# Sheet1.net
KiCad netlist of a schematic drawn in Altium Designer
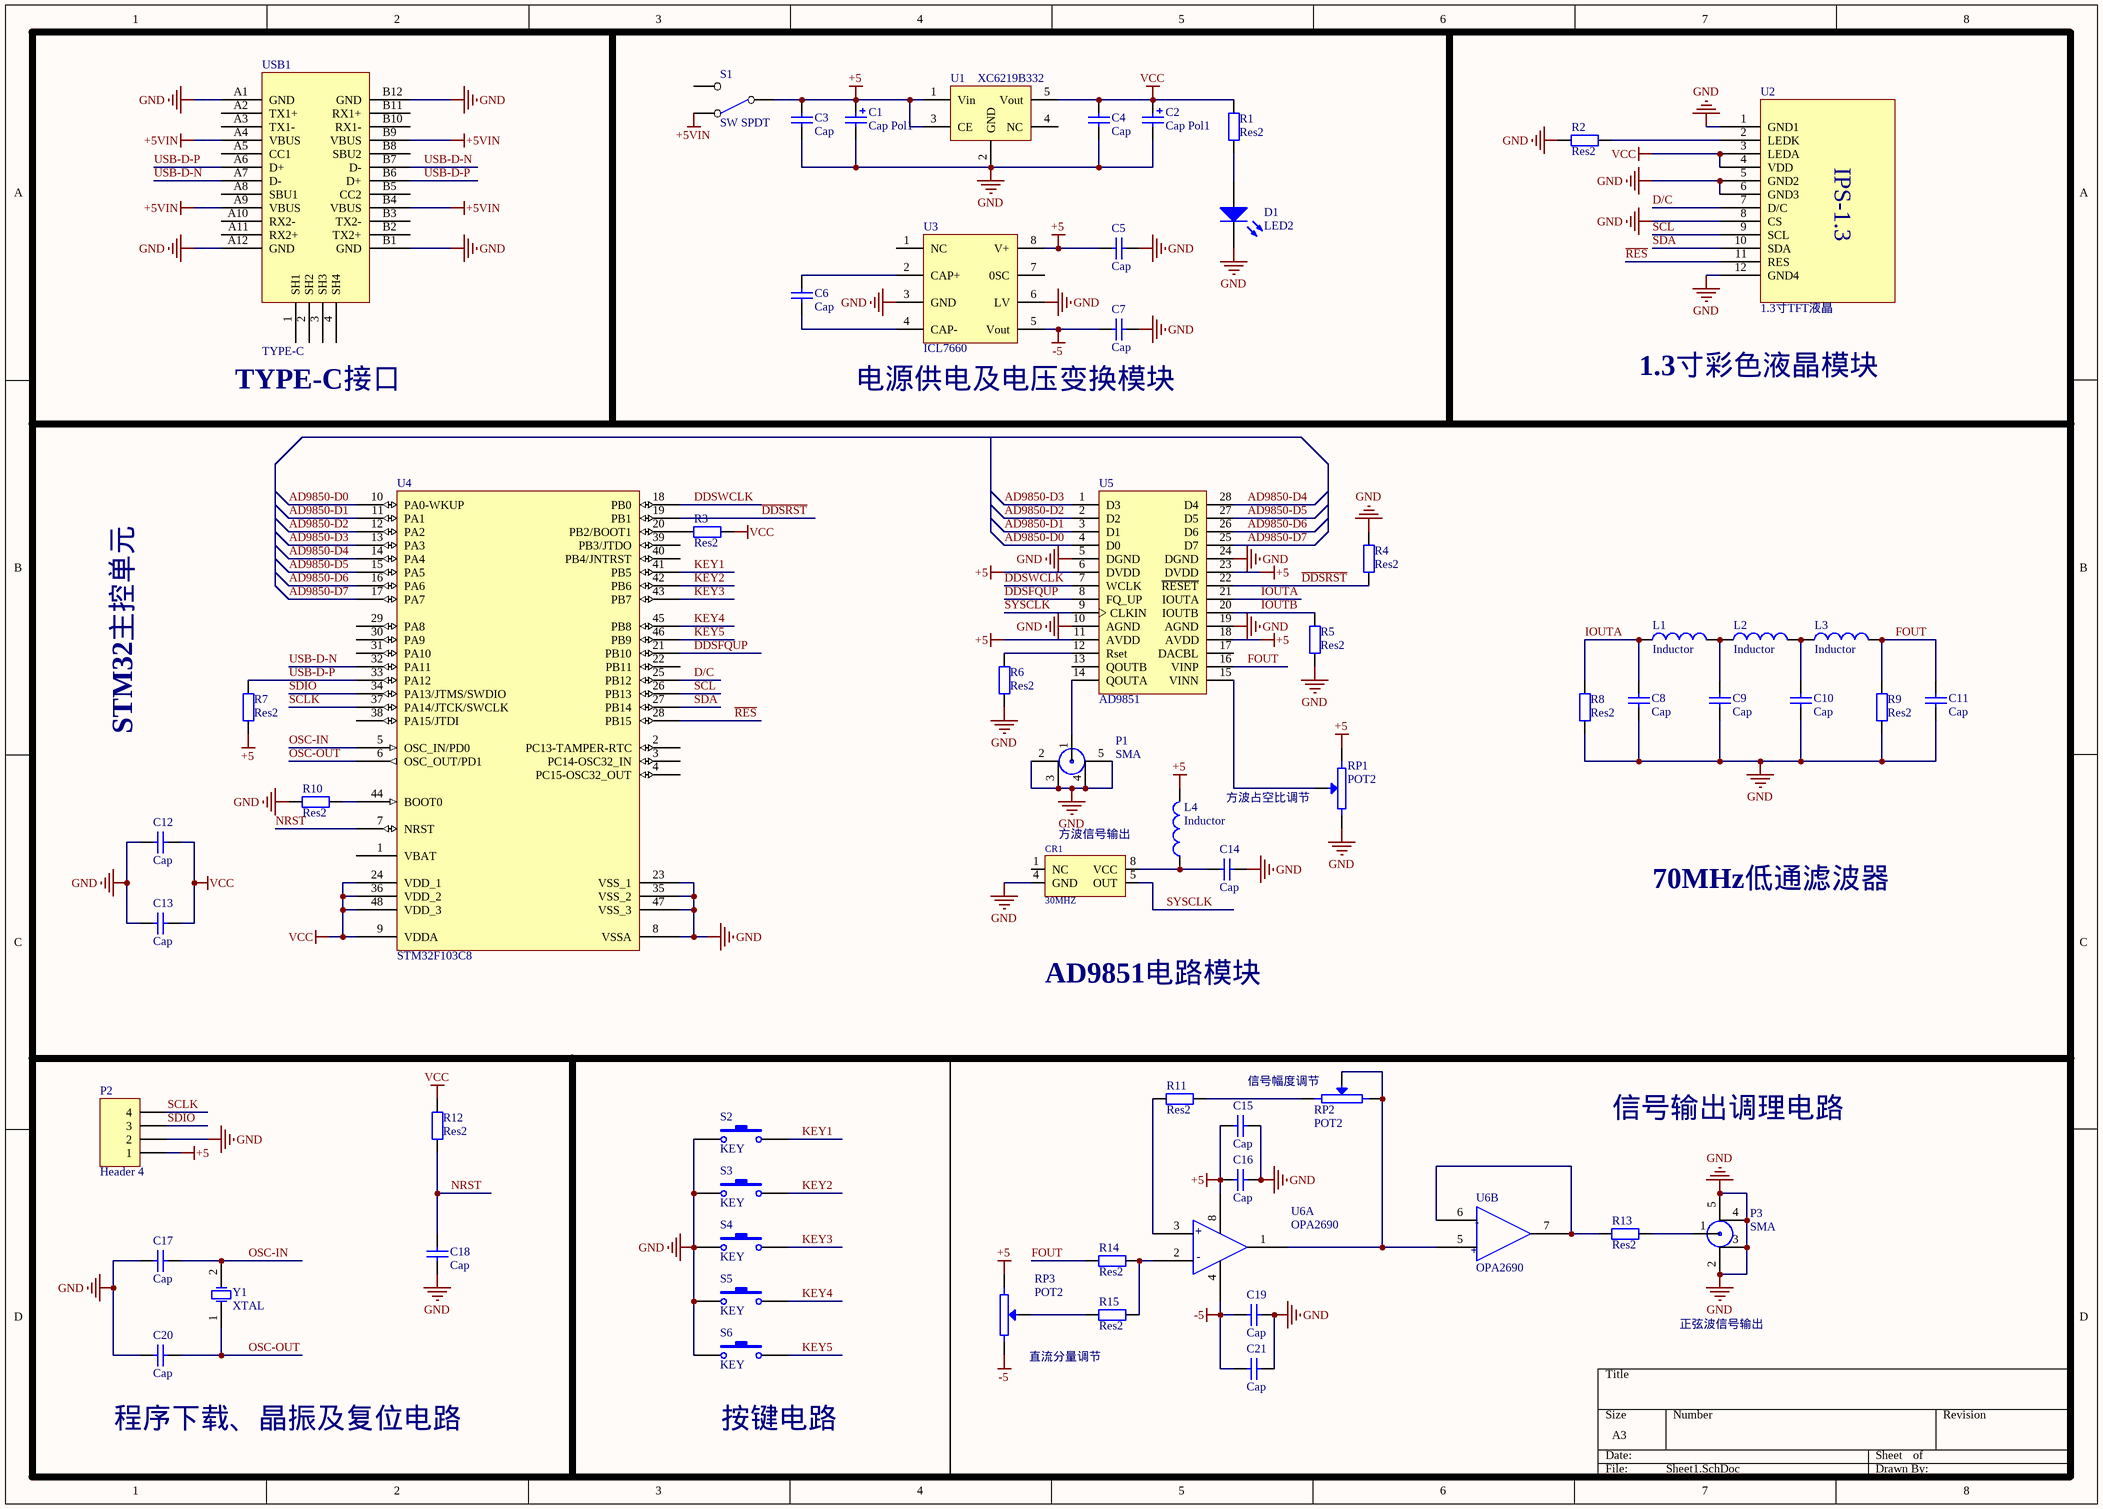
[diagram p0: Sheet1.SchDoc]

(export (version "E")
  (design (tool "Eeschema 10.0.6"))
  (components
    (comp (ref "C1")
      (value "Cap Pol1")
      (footprint "C1210_N")
      (description "Polarized Capacitor (Radial)")
      (fields (field (name "PUBLISHER") "Altium Limited"))
      (libsource (lib "基于STM32的DDS信号源设计实例") (part "Cap Pol1"))
    )
    (comp (ref "C2")
      (value "Cap Pol1")
      (description "Polarized Capacitor (Radial)")
      (fields (field (name "PUBLISHER") "Altium Limited"))
      (libsource (lib "基于STM32的DDS信号源设计实例") (part "Cap Pol1"))
    )
    (comp (ref "C3")
      (value "Cap")
      (footprint "C0805")
      (description "Capacitor")
      (fields (field (name "PUBLISHER") "Altium Limited"))
      (libsource (lib "基于STM32的DDS信号源设计实例") (part "Cap"))
    )
    (comp (ref "C4")
      (value "Cap")
      (footprint "C0805")
      (description "Capacitor")
      (fields (field (name "PUBLISHER") "Altium Limited"))
      (libsource (lib "基于STM32的DDS信号源设计实例") (part "Cap"))
    )
    (comp (ref "C5")
      (value "Cap")
      (footprint "C0805")
      (description "Capacitor")
      (fields (field (name "PUBLISHER") "Altium Limited"))
      (libsource (lib "基于STM32的DDS信号源设计实例") (part "Cap"))
    )
    (comp (ref "C6")
      (value "Cap")
      (footprint "C0805")
      (description "Capacitor")
      (fields (field (name "PUBLISHER") "Altium Limited"))
      (libsource (lib "基于STM32的DDS信号源设计实例") (part "Cap"))
    )
    (comp (ref "C7")
      (value "Cap")
      (footprint "C0805")
      (description "Capacitor")
      (fields (field (name "PUBLISHER") "Altium Limited"))
      (libsource (lib "基于STM32的DDS信号源设计实例") (part "Cap"))
    )
    (comp (ref "C8")
      (value "Cap")
      (footprint "C0805")
      (description "Capacitor")
      (fields (field (name "PUBLISHER") "Altium Limited"))
      (libsource (lib "基于STM32的DDS信号源设计实例") (part "Cap"))
    )
    (comp (ref "C9")
      (value "Cap")
      (footprint "C0805")
      (description "Capacitor")
      (fields (field (name "PUBLISHER") "Altium Limited"))
      (libsource (lib "基于STM32的DDS信号源设计实例") (part "Cap"))
    )
    (comp (ref "C10")
      (value "Cap")
      (footprint "C0805")
      (description "Capacitor")
      (fields (field (name "PUBLISHER") "Altium Limited"))
      (libsource (lib "基于STM32的DDS信号源设计实例") (part "Cap"))
    )
    (comp (ref "C11")
      (value "Cap")
      (footprint "C0805")
      (description "Capacitor")
      (fields (field (name "PUBLISHER") "Altium Limited"))
      (libsource (lib "基于STM32的DDS信号源设计实例") (part "Cap"))
    )
    (comp (ref "C12")
      (value "Cap")
      (footprint "C0805")
      (description "Capacitor")
      (fields (field (name "PUBLISHER") "Altium Limited"))
      (libsource (lib "基于STM32的DDS信号源设计实例") (part "Cap"))
    )
    (comp (ref "C13")
      (value "Cap")
      (footprint "C0805")
      (description "Capacitor")
      (fields (field (name "PUBLISHER") "Altium Limited"))
      (libsource (lib "基于STM32的DDS信号源设计实例") (part "Cap"))
    )
    (comp (ref "C14")
      (value "Cap")
      (footprint "C0805")
      (description "Capacitor")
      (fields (field (name "PUBLISHER") "Altium Limited"))
      (libsource (lib "基于STM32的DDS信号源设计实例") (part "Cap"))
    )
    (comp (ref "C15")
      (value "Cap")
      (footprint "C0805")
      (description "Capacitor")
      (fields (field (name "PUBLISHER") "Altium Limited"))
      (libsource (lib "基于STM32的DDS信号源设计实例") (part "Cap"))
    )
    (comp (ref "C16")
      (value "Cap")
      (footprint "C0805")
      (description "Capacitor")
      (fields (field (name "PUBLISHER") "Altium Limited"))
      (libsource (lib "基于STM32的DDS信号源设计实例") (part "Cap"))
    )
    (comp (ref "C17")
      (value "Cap")
      (footprint "C0805")
      (description "Capacitor")
      (fields (field (name "PUBLISHER") "Altium Limited"))
      (libsource (lib "基于STM32的DDS信号源设计实例") (part "Cap"))
    )
    (comp (ref "C18")
      (value "Cap")
      (footprint "C0805")
      (description "Capacitor")
      (fields (field (name "PUBLISHER") "Altium Limited"))
      (libsource (lib "基于STM32的DDS信号源设计实例") (part "Cap"))
    )
    (comp (ref "C19")
      (value "Cap")
      (footprint "C0805")
      (description "Capacitor")
      (fields (field (name "PUBLISHER") "Altium Limited"))
      (libsource (lib "基于STM32的DDS信号源设计实例") (part "Cap"))
    )
    (comp (ref "C20")
      (value "Cap")
      (footprint "C0805")
      (description "Capacitor")
      (fields (field (name "PUBLISHER") "Altium Limited"))
      (libsource (lib "基于STM32的DDS信号源设计实例") (part "Cap"))
    )
    (comp (ref "C21")
      (value "Cap")
      (footprint "C0805")
      (description "Capacitor")
      (fields (field (name "PUBLISHER") "Altium Limited"))
      (libsource (lib "基于STM32的DDS信号源设计实例") (part "Cap"))
    )
    (comp (ref "CR1")
      (value "30MHZ")
      (footprint "CRYSTAL-SMT-5X7")
      (libsource (lib "基于STM32的DDS信号源设计实例") (part "CRYSTAL-DIP8"))
    )
    (comp (ref "D1")
      (value "LED2")
      (footprint "3.2X1.6X1.1")
      (description "Typical RED, GREEN, YELLOW, AMBER GaAs LED")
      (fields (field (name "PUBLISHER") "Altium Limited"))
      (libsource (lib "Miscellaneous Devices") (part "LED2"))
    )
    (comp (ref "L1")
      (value "Inductor")
      (footprint "6-0805_N")
      (fields (field (name "PUBLISHER") "Altium Limited"))
      (libsource (lib "基于STM32的DDS信号源设计实例") (part "Inductor"))
    )
    (comp (ref "L2")
      (value "Inductor")
      (footprint "6-0805_N")
      (fields (field (name "PUBLISHER") "Altium Limited"))
      (libsource (lib "基于STM32的DDS信号源设计实例") (part "Inductor"))
    )
    (comp (ref "L3")
      (value "Inductor")
      (footprint "6-0805_N")
      (fields (field (name "PUBLISHER") "Altium Limited"))
      (libsource (lib "基于STM32的DDS信号源设计实例") (part "Inductor"))
    )
    (comp (ref "L4")
      (value "Inductor")
      (footprint "6-0805_N")
      (fields (field (name "PUBLISHER") "Altium Limited"))
      (libsource (lib "基于STM32的DDS信号源设计实例") (part "Inductor"))
    )
    (comp (ref "P1") (value "SMA") (footprint "SMA-KE") (libsource (lib "Schlib1") (part "SMA")))
    (comp (ref "P2")
      (value "Header 4")
      (footprint "HDR1X4")
      (description "Header, 4-Pin")
      (fields (field (name "PUBLISHER") "Altium Limited"))
      (libsource (lib "Miscellaneous Connectors") (part "Header 4"))
    )
    (comp (ref "P3") (value "SMA") (footprint "SMA-KE") (libsource (lib "Schlib1") (part "SMA")))
    (comp (ref "R1")
      (value "Res2")
      (footprint "6-0805_N")
      (description "Resistor")
      (fields (field (name "PUBLISHER") "Altium Limited"))
      (libsource (lib "基于STM32的DDS信号源设计实例") (part "Res2"))
    )
    (comp (ref "R2")
      (value "Res2")
      (footprint "6-0805_N")
      (description "Resistor")
      (fields (field (name "PUBLISHER") "Altium Limited"))
      (libsource (lib "") (part "Res2_2"))
    )
    (comp (ref "R3")
      (value "Res2")
      (footprint "6-0805_N")
      (description "Resistor")
      (fields (field (name "PUBLISHER") "Altium Limited"))
      (libsource (lib "") (part "Res2_2"))
    )
    (comp (ref "R4")
      (value "Res2")
      (footprint "6-0805_N")
      (description "Resistor")
      (fields (field (name "PUBLISHER") "Altium Limited"))
      (libsource (lib "基于STM32的DDS信号源设计实例") (part "Res2"))
    )
    (comp (ref "R5")
      (value "Res2")
      (footprint "6-0805_N")
      (description "Resistor")
      (fields (field (name "PUBLISHER") "Altium Limited"))
      (libsource (lib "基于STM32的DDS信号源设计实例") (part "Res2"))
    )
    (comp (ref "R6")
      (value "Res2")
      (footprint "6-0805_N")
      (description "Resistor")
      (fields (field (name "PUBLISHER") "Altium Limited"))
      (libsource (lib "基于STM32的DDS信号源设计实例") (part "Res2"))
    )
    (comp (ref "R7")
      (value "Res2")
      (footprint "6-0805_N")
      (description "Resistor")
      (fields (field (name "PUBLISHER") "Altium Limited"))
      (libsource (lib "基于STM32的DDS信号源设计实例") (part "Res2"))
    )
    (comp (ref "R8")
      (value "Res2")
      (footprint "6-0805_N")
      (description "Resistor")
      (fields (field (name "PUBLISHER") "Altium Limited"))
      (libsource (lib "基于STM32的DDS信号源设计实例") (part "Res2"))
    )
    (comp (ref "R9")
      (value "Res2")
      (footprint "6-0805_N")
      (description "Resistor")
      (fields (field (name "PUBLISHER") "Altium Limited"))
      (libsource (lib "基于STM32的DDS信号源设计实例") (part "Res2"))
    )
    (comp (ref "R10")
      (value "Res2")
      (footprint "6-0805_N")
      (description "Resistor")
      (fields (field (name "PUBLISHER") "Altium Limited"))
      (libsource (lib "") (part "Res2_2"))
    )
    (comp (ref "R11")
      (value "Res2")
      (footprint "6-0805_N")
      (description "Resistor")
      (fields (field (name "PUBLISHER") "Altium Limited"))
      (libsource (lib "") (part "Res2_1"))
    )
    (comp (ref "R12")
      (value "Res2")
      (footprint "6-0805_N")
      (description "Resistor")
      (fields (field (name "PUBLISHER") "Altium Limited"))
      (libsource (lib "基于STM32的DDS信号源设计实例") (part "Res2"))
    )
    (comp (ref "R13")
      (value "Res2")
      (footprint "6-0805_N")
      (description "Resistor")
      (fields (field (name "PUBLISHER") "Altium Limited"))
      (libsource (lib "") (part "Res2_1"))
    )
    (comp (ref "R14")
      (value "Res2")
      (footprint "6-0805_N")
      (description "Resistor")
      (fields (field (name "PUBLISHER") "Altium Limited"))
      (libsource (lib "") (part "Res2_1"))
    )
    (comp (ref "R15")
      (value "Res2")
      (footprint "6-0805_N")
      (description "Resistor")
      (fields (field (name "PUBLISHER") "Altium Limited"))
      (libsource (lib "") (part "Res2_1"))
    )
    (comp (ref "RP1")
      (value "POT2")
      (footprint "VR7")
      (description "Potentiometer")
      (libsource (lib "基于STM32的DDS信号源设计实例") (part "POT2"))
    )
    (comp (ref "RP2")
      (value "POT2")
      (footprint "VR7")
      (description "Potentiometer")
      (libsource (lib "基于STM32的DDS信号源设计实例") (part "POT2"))
    )
    (comp (ref "RP3")
      (value "POT2")
      (footprint "VR7")
      (description "Potentiometer")
      (libsource (lib "基于STM32的DDS信号源设计实例") (part "POT2"))
    )
    (comp (ref "S1")
      (value "SW SPDT")
      (footprint "SW-SPDT-7P")
      (libsource (lib "基于STM32的DDS信号源设计实例") (part "SW SPDT"))
    )
    (comp (ref "S2")
      (value "KEY")
      (footprint "SW-MINI")
      (description "Switch")
      (fields (field (name "PUBLISHER") "Altium Limited"))
      (libsource (lib "基于STM32的DDS信号源设计实例") (part "SW-PB"))
    )
    (comp (ref "S3")
      (value "KEY")
      (footprint "SW-MINI")
      (description "Switch")
      (fields (field (name "PUBLISHER") "Altium Limited"))
      (libsource (lib "基于STM32的DDS信号源设计实例") (part "SW-PB"))
    )
    (comp (ref "S4")
      (value "KEY")
      (footprint "SW-MINI")
      (description "Switch")
      (fields (field (name "PUBLISHER") "Altium Limited"))
      (libsource (lib "基于STM32的DDS信号源设计实例") (part "SW-PB"))
    )
    (comp (ref "S5")
      (value "KEY")
      (footprint "SW-MINI")
      (description "Switch")
      (fields (field (name "PUBLISHER") "Altium Limited"))
      (libsource (lib "基于STM32的DDS信号源设计实例") (part "SW-PB"))
    )
    (comp (ref "S6")
      (value "KEY")
      (footprint "SW-MINI")
      (description "Switch")
      (fields (field (name "PUBLISHER") "Altium Limited"))
      (libsource (lib "基于STM32的DDS信号源设计实例") (part "SW-PB"))
    )
    (comp (ref "U1")
      (value "XC6219B332")
      (footprint "SOT23-5L")
      (libsource (lib "基于STM32的DDS信号源设计实例") (part "XC6219"))
    )
    (comp (ref "U2")
      (value "1.3寸TFT液晶")
      (footprint "1.3-TFT-TPS")
      (libsource (lib "基于STM32的DDS信号源设计实例") (part "1.3寸TFT液晶"))
    )
    (comp (ref "U3")
      (value "ICL7660")
      (footprint "SO8_N")
      (libsource (lib "基于STM32的DDS信号源设计实例") (part "ICL7660"))
    )
    (comp (ref "U4")
      (value "STM32F103C8")
      (footprint "TQFP-48")
      (description "Flaah:64/RAM:20/IO:36")
      (fields (field (name "版权归属") "源创客"))
      (libsource (lib "基于STM32的DDS信号源设计实例") (part "STM32F103C8"))
    )
    (comp (ref "U5") (value "AD9851") (footprint "TSSOP28") (libsource (lib "Schlib1") (part "AD9851")))
    (comp (ref "U6") (value "OPA2690") (footprint "SO-8") (libsource (lib "Schlib1") (part "OPA2690")))
    (comp (ref "USB1")
      (value "TYPE-C")
      (footprint "TYPE-C")
      (libsource (lib "基于STM32的DDS信号源设计实例") (part "TYPE-C"))
    )
    (comp (ref "Y1")
      (value "XTAL")
      (footprint "XTAL2")
      (description "Crystal Oscillator")
      (fields (field (name "PUBLISHER") "Altium Limited"))
      (libsource (lib "基于STM32的DDS信号源设计实例") (part "XTAL"))
    )
  )
  (nets
    (net (code "1") (name "+5") (class "Default")
      (node (ref "C1") (pin "1") (pinfunction "1_1") (pintype "passive"))
      (node (ref "C15") (pin "1") (pinfunction "1_1") (pintype "passive"))
      (node (ref "C16") (pin "1") (pinfunction "1_1") (pintype "passive"))
      (node (ref "C3") (pin "2") (pinfunction "2_2") (pintype "passive"))
      (node (ref "C5") (pin "2") (pinfunction "2_2") (pintype "passive"))
      (node (ref "L4") (pin "2") (pinfunction "2_2") (pintype "passive"))
      (node (ref "P2") (pin "1") (pinfunction "1_1") (pintype "passive"))
      (node (ref "R7") (pin "1") (pinfunction "1_1") (pintype "passive"))
      (node (ref "RP1") (pin "2") (pinfunction "2_2") (pintype "passive"))
      (node (ref "RP3") (pin "1") (pinfunction "1_1") (pintype "passive"))
      (node (ref "S1") (pin "2") (pinfunction "COMMON_2") (pintype "passive"))
      (node (ref "U1") (pin "1") (pinfunction "Vin_1") (pintype "passive"))
      (node (ref "U1") (pin "3") (pinfunction "CE_3") (pintype "passive"))
      (node (ref "U3") (pin "8") (pinfunction "V+_8") (pintype "passive"))
      (node (ref "U5") (pin "11") (pinfunction "AVDD_11") (pintype "passive"))
      (node (ref "U5") (pin "18") (pinfunction "AVDD_18") (pintype "passive"))
      (node (ref "U5") (pin "23") (pinfunction "DVDD_23") (pintype "passive"))
      (node (ref "U5") (pin "6") (pinfunction "DVDD_6") (pintype "passive"))
      (node (ref "U6") (pin "8") (pintype "passive"))
    )
    (net (code "2") (name "+5VIN") (class "Default")
      (node (ref "S1") (pin "1") (pinfunction "NC_1") (pintype "passive"))
      (node (ref "USB1") (pin "A4") (pinfunction "VBUS_A4") (pintype "passive"))
      (node (ref "USB1") (pin "A9") (pinfunction "VBUS_A9") (pintype "passive"))
      (node (ref "USB1") (pin "B4") (pinfunction "VBUS_B4") (pintype "passive"))
      (node (ref "USB1") (pin "B9") (pinfunction "VBUS_B9") (pintype "passive"))
    )
    (net (code "3") (name "-5") (class "Default")
      (node (ref "C19") (pin "1") (pinfunction "1_1") (pintype "passive"))
      (node (ref "C21") (pin "1") (pinfunction "1_1") (pintype "passive"))
      (node (ref "C7") (pin "2") (pinfunction "2_2") (pintype "passive"))
      (node (ref "RP3") (pin "2") (pinfunction "2_2") (pintype "passive"))
      (node (ref "U3") (pin "5") (pinfunction "Vout_5") (pintype "passive"))
      (node (ref "U6") (pin "4") (pintype "passive"))
    )
    (net (code "4") (name "/AD9850-D0") (class "Default")
      (node (ref "U4") (pin "10") (pinfunction "PA0-WKUP_10") (pintype "bidirectional"))
      (node (ref "U5") (pin "4") (pinfunction "D0_4") (pintype "passive"))
    )
    (net (code "5") (name "/AD9850-D1") (class "Default")
      (node (ref "U4") (pin "11") (pinfunction "PA1_11") (pintype "bidirectional"))
      (node (ref "U5") (pin "3") (pinfunction "D1_3") (pintype "passive"))
    )
    (net (code "6") (name "/AD9850-D2") (class "Default")
      (node (ref "U4") (pin "12") (pinfunction "PA2_12") (pintype "bidirectional"))
      (node (ref "U5") (pin "2") (pinfunction "D2_2") (pintype "passive"))
    )
    (net (code "7") (name "/AD9850-D3") (class "Default")
      (node (ref "U4") (pin "13") (pinfunction "PA3_13") (pintype "bidirectional"))
      (node (ref "U5") (pin "1") (pinfunction "D3_1") (pintype "passive"))
    )
    (net (code "8") (name "/AD9850-D4") (class "Default")
      (node (ref "U4") (pin "14") (pinfunction "PA4_14") (pintype "bidirectional"))
      (node (ref "U5") (pin "28") (pinfunction "D4_28") (pintype "passive"))
    )
    (net (code "9") (name "/AD9850-D5") (class "Default")
      (node (ref "U4") (pin "15") (pinfunction "PA5_15") (pintype "bidirectional"))
      (node (ref "U5") (pin "27") (pinfunction "D5_27") (pintype "passive"))
    )
    (net (code "10") (name "/AD9850-D6") (class "Default")
      (node (ref "U4") (pin "16") (pinfunction "PA6_16") (pintype "bidirectional"))
      (node (ref "U5") (pin "26") (pinfunction "D6_26") (pintype "passive"))
    )
    (net (code "11") (name "/AD9850-D7") (class "Default")
      (node (ref "U4") (pin "17") (pinfunction "PA7_17") (pintype "bidirectional"))
      (node (ref "U5") (pin "25") (pinfunction "D7_25") (pintype "passive"))
    )
    (net (code "12") (name "/DDSFQUP") (class "Default")
      (node (ref "U4") (pin "21") (pinfunction "PB10_21") (pintype "bidirectional"))
      (node (ref "U5") (pin "8") (pinfunction "FQ_UP_8") (pintype "passive"))
    )
    (net (code "13") (name "/DDSWCLK") (class "Default")
      (node (ref "U4") (pin "18") (pinfunction "PB0_18") (pintype "bidirectional"))
      (node (ref "U5") (pin "7") (pinfunction "WCLK_7") (pintype "passive"))
    )
    (net (code "14") (name "/D{slash}C") (class "Default")
      (node (ref "U2") (pin "7") (pinfunction "D/C_7") (pintype "passive"))
      (node (ref "U4") (pin "25") (pinfunction "PB12_25") (pintype "bidirectional"))
    )
    (net (code "15") (name "/FOUT") (class "Default")
      (node (ref "C11") (pin "2") (pinfunction "2_2") (pintype "passive"))
      (node (ref "L3") (pin "2") (pinfunction "2_2") (pintype "passive"))
      (node (ref "R14") (pin "1") (pinfunction "1_1") (pintype "passive"))
      (node (ref "R9") (pin "2") (pinfunction "2_2") (pintype "passive"))
      (node (ref "U5") (pin "16") (pinfunction "VINP_16") (pintype "passive"))
    )
    (net (code "16") (name "/IOUTA") (class "Default")
      (node (ref "C8") (pin "2") (pinfunction "2_2") (pintype "passive"))
      (node (ref "L1") (pin "1") (pinfunction "1_1") (pintype "passive"))
      (node (ref "R8") (pin "2") (pinfunction "2_2") (pintype "passive"))
      (node (ref "U5") (pin "21") (pinfunction "IOUTA_21") (pintype "passive"))
    )
    (net (code "17") (name "/IOUTB") (class "Default")
      (node (ref "R5") (pin "2") (pinfunction "2_2") (pintype "passive"))
      (node (ref "U5") (pin "20") (pinfunction "IOUTB_20") (pintype "passive"))
    )
    (net (code "18") (name "/KEY1") (class "Default")
      (node (ref "S2") (pin "2") (pinfunction "2_2") (pintype "passive"))
      (node (ref "U4") (pin "41") (pinfunction "PB5_41") (pintype "bidirectional"))
    )
    (net (code "19") (name "/KEY2") (class "Default")
      (node (ref "S3") (pin "2") (pinfunction "2_2") (pintype "passive"))
      (node (ref "U4") (pin "42") (pinfunction "PB6_42") (pintype "bidirectional"))
    )
    (net (code "20") (name "/KEY3") (class "Default")
      (node (ref "S4") (pin "2") (pinfunction "2_2") (pintype "passive"))
      (node (ref "U4") (pin "43") (pinfunction "PB7_43") (pintype "bidirectional"))
    )
    (net (code "21") (name "/KEY4") (class "Default")
      (node (ref "S5") (pin "2") (pinfunction "2_2") (pintype "passive"))
      (node (ref "U4") (pin "45") (pinfunction "PB8_45") (pintype "bidirectional"))
    )
    (net (code "22") (name "/KEY5") (class "Default")
      (node (ref "S6") (pin "2") (pinfunction "2_2") (pintype "passive"))
      (node (ref "U4") (pin "46") (pinfunction "PB9_46") (pintype "bidirectional"))
    )
    (net (code "23") (name "/NRST") (class "Default")
      (node (ref "C18") (pin "2") (pinfunction "2_2") (pintype "passive"))
      (node (ref "R12") (pin "1") (pinfunction "1_1") (pintype "passive"))
      (node (ref "U4") (pin "7") (pinfunction "NRST_7") (pintype "bidirectional"))
    )
    (net (code "24") (name "/OSC-IN") (class "Default")
      (node (ref "C17") (pin "2") (pinfunction "2_2") (pintype "passive"))
      (node (ref "U4") (pin "5") (pinfunction "OSC_IN/PD0_5") (pintype "input"))
      (node (ref "Y1") (pin "2") (pinfunction "OSC2_2") (pintype "passive"))
    )
    (net (code "25") (name "/OSC-OUT") (class "Default")
      (node (ref "C20") (pin "2") (pinfunction "2_2") (pintype "passive"))
      (node (ref "U4") (pin "6") (pinfunction "OSC_OUT/PD1_6") (pintype "output"))
      (node (ref "Y1") (pin "1") (pinfunction "OSC1_1") (pintype "passive"))
    )
    (net (code "26") (name "/SCL") (class "Default")
      (node (ref "U2") (pin "9") (pinfunction "SCL_9") (pintype "passive"))
      (node (ref "U4") (pin "26") (pinfunction "PB13_26") (pintype "bidirectional"))
    )
    (net (code "27") (name "/SCLK") (class "Default")
      (node (ref "P2") (pin "4") (pinfunction "4_4") (pintype "passive"))
      (node (ref "U4") (pin "37") (pinfunction "PA14/JTCK/SWCLK_37") (pintype "bidirectional"))
    )
    (net (code "28") (name "/SDA") (class "Default")
      (node (ref "U2") (pin "10") (pinfunction "SDA_10") (pintype "passive"))
      (node (ref "U4") (pin "27") (pinfunction "PB14_27") (pintype "bidirectional"))
    )
    (net (code "29") (name "/SDIO") (class "Default")
      (node (ref "P2") (pin "3") (pinfunction "3_3") (pintype "passive"))
      (node (ref "U4") (pin "34") (pinfunction "PA13/JTMS/SWDIO_34") (pintype "bidirectional"))
    )
    (net (code "30") (name "/SYSCLK") (class "Default")
      (node (ref "CR1") (pin "5") (pinfunction "OUT_5") (pintype "passive"))
      (node (ref "U5") (pin "9") (pinfunction "CLKIN_9") (pintype "passive"))
    )
    (net (code "31") (name "/USB-D-N") (class "Default")
      (node (ref "U4") (pin "32") (pinfunction "PA11_32") (pintype "bidirectional"))
      (node (ref "USB1") (pin "A7") (pinfunction "D-_A7") (pintype "passive"))
      (node (ref "USB1") (pin "B7") (pinfunction "D-_B7") (pintype "passive"))
    )
    (net (code "32") (name "/USB-D-P") (class "Default")
      (node (ref "R7") (pin "2") (pinfunction "2_2") (pintype "passive"))
      (node (ref "U4") (pin "33") (pinfunction "PA12_33") (pintype "bidirectional"))
      (node (ref "USB1") (pin "A6") (pinfunction "D+_A6") (pintype "passive"))
      (node (ref "USB1") (pin "B6") (pinfunction "D+_B6") (pintype "passive"))
    )
    (net (code "33") (name "/~{DDSRST}") (class "Default")
      (node (ref "R4") (pin "1") (pinfunction "1_1") (pintype "passive"))
      (node (ref "U4") (pin "19") (pinfunction "PB1_19") (pintype "bidirectional"))
      (node (ref "U5") (pin "22") (pinfunction "~{RESET}_22") (pintype "passive"))
    )
    (net (code "34") (name "/~{RES}") (class "Default")
      (node (ref "U2") (pin "11") (pinfunction "RES_11") (pintype "passive"))
      (node (ref "U4") (pin "28") (pinfunction "PB15_28") (pintype "bidirectional"))
    )
    (net (code "35") (name "GND") (class "Default")
      (node (ref "C1") (pin "2") (pinfunction "2_2") (pintype "passive"))
      (node (ref "C10") (pin "1") (pinfunction "1_1") (pintype "passive"))
      (node (ref "C11") (pin "1") (pinfunction "1_1") (pintype "passive"))
      (node (ref "C12") (pin "1") (pinfunction "1_1") (pintype "passive"))
      (node (ref "C13") (pin "1") (pinfunction "1_1") (pintype "passive"))
      (node (ref "C14") (pin "2") (pinfunction "2_2") (pintype "passive"))
      (node (ref "C15") (pin "2") (pinfunction "2_2") (pintype "passive"))
      (node (ref "C16") (pin "2") (pinfunction "2_2") (pintype "passive"))
      (node (ref "C17") (pin "1") (pinfunction "1_1") (pintype "passive"))
      (node (ref "C18") (pin "1") (pinfunction "1_1") (pintype "passive"))
      (node (ref "C19") (pin "2") (pinfunction "2_2") (pintype "passive"))
      (node (ref "C2") (pin "2") (pinfunction "2_2") (pintype "passive"))
      (node (ref "C20") (pin "1") (pinfunction "1_1") (pintype "passive"))
      (node (ref "C21") (pin "2") (pinfunction "2_2") (pintype "passive"))
      (node (ref "C3") (pin "1") (pinfunction "1_1") (pintype "passive"))
      (node (ref "C4") (pin "1") (pinfunction "1_1") (pintype "passive"))
      (node (ref "C5") (pin "1") (pinfunction "1_1") (pintype "passive"))
      (node (ref "C7") (pin "1") (pinfunction "1_1") (pintype "passive"))
      (node (ref "C8") (pin "1") (pinfunction "1_1") (pintype "passive"))
      (node (ref "C9") (pin "1") (pinfunction "1_1") (pintype "passive"))
      (node (ref "CR1") (pin "4") (pinfunction "GND_4") (pintype "passive"))
      (node (ref "D1") (pin "2") (pinfunction "K_2") (pintype "passive"))
      (node (ref "P1") (pin "2") (pintype "passive"))
      (node (ref "P1") (pin "3") (pintype "passive"))
      (node (ref "P1") (pin "4") (pintype "passive"))
      (node (ref "P1") (pin "5") (pintype "passive"))
      (node (ref "P2") (pin "2") (pinfunction "2_2") (pintype "passive"))
      (node (ref "P3") (pin "2") (pintype "passive"))
      (node (ref "P3") (pin "3") (pintype "passive"))
      (node (ref "P3") (pin "4") (pintype "passive"))
      (node (ref "P3") (pin "5") (pintype "passive"))
      (node (ref "R10") (pin "2") (pinfunction "2_2") (pintype "passive"))
      (node (ref "R2") (pin "2") (pinfunction "2_2") (pintype "passive"))
      (node (ref "R4") (pin "2") (pinfunction "2_2") (pintype "passive"))
      (node (ref "R5") (pin "1") (pinfunction "1_1") (pintype "passive"))
      (node (ref "R6") (pin "1") (pinfunction "1_1") (pintype "passive"))
      (node (ref "R8") (pin "1") (pinfunction "1_1") (pintype "passive"))
      (node (ref "R9") (pin "1") (pinfunction "1_1") (pintype "passive"))
      (node (ref "RP1") (pin "1") (pinfunction "1_1") (pintype "passive"))
      (node (ref "S2") (pin "1") (pinfunction "1_1") (pintype "passive"))
      (node (ref "S3") (pin "1") (pinfunction "1_1") (pintype "passive"))
      (node (ref "S4") (pin "1") (pinfunction "1_1") (pintype "passive"))
      (node (ref "S5") (pin "1") (pinfunction "1_1") (pintype "passive"))
      (node (ref "S6") (pin "1") (pinfunction "1_1") (pintype "passive"))
      (node (ref "U1") (pin "2") (pinfunction "GND_2") (pintype "power_in"))
      (node (ref "U2") (pin "1") (pinfunction "GND1_1") (pintype "passive"))
      (node (ref "U2") (pin "12") (pinfunction "GND4_12") (pintype "passive"))
      (node (ref "U2") (pin "5") (pinfunction "GND2_5") (pintype "passive"))
      (node (ref "U2") (pin "6") (pinfunction "GND3_6") (pintype "passive"))
      (node (ref "U2") (pin "8") (pinfunction "CS_8") (pintype "passive"))
      (node (ref "U3") (pin "3") (pinfunction "GND_3") (pintype "passive"))
      (node (ref "U3") (pin "6") (pinfunction "LV_6") (pintype "passive"))
      (node (ref "U4") (pin "23") (pinfunction "VSS_1_23") (pintype "power_in"))
      (node (ref "U4") (pin "35") (pinfunction "VSS_2_35") (pintype "power_in"))
      (node (ref "U4") (pin "47") (pinfunction "VSS_3_47") (pintype "power_in"))
      (node (ref "U4") (pin "8") (pinfunction "VSSA_8") (pintype "power_in"))
      (node (ref "U5") (pin "10") (pinfunction "AGND_10") (pintype "passive"))
      (node (ref "U5") (pin "19") (pinfunction "AGND_19") (pintype "passive"))
      (node (ref "U5") (pin "24") (pinfunction "DGND_24") (pintype "passive"))
      (node (ref "U5") (pin "5") (pinfunction "DGND_5") (pintype "passive"))
      (node (ref "USB1") (pin "A1") (pinfunction "GND_A1") (pintype "passive"))
      (node (ref "USB1") (pin "A12") (pinfunction "GND_A12") (pintype "passive"))
      (node (ref "USB1") (pin "B1") (pinfunction "GND_B1") (pintype "passive"))
      (node (ref "USB1") (pin "B12") (pinfunction "GND_B12") (pintype "passive"))
    )
    (net (code "36") (name "Net-(C9-Pad2)") (class "Default")
      (node (ref "C9") (pin "2") (pinfunction "2_2") (pintype "passive"))
      (node (ref "L1") (pin "2") (pinfunction "2_2") (pintype "passive"))
      (node (ref "L2") (pin "1") (pinfunction "1_1") (pintype "passive"))
    )
    (net (code "37") (name "Net-(C10-Pad2)") (class "Default")
      (node (ref "C10") (pin "2") (pinfunction "2_2") (pintype "passive"))
      (node (ref "L2") (pin "2") (pinfunction "2_2") (pintype "passive"))
      (node (ref "L3") (pin "1") (pinfunction "1_1") (pintype "passive"))
    )
    (net (code "38") (name "Net-(CR1-VCC)") (class "Default")
      (node (ref "C14") (pin "1") (pinfunction "1_1") (pintype "passive"))
      (node (ref "CR1") (pin "8") (pinfunction "VCC_8") (pintype "passive"))
      (node (ref "L4") (pin "1") (pinfunction "1_1") (pintype "passive"))
    )
    (net (code "39") (name "Net-(D1-A)") (class "Default")
      (node (ref "D1") (pin "1") (pinfunction "A_1") (pintype "passive"))
      (node (ref "R1") (pin "1") (pinfunction "1_1") (pintype "passive"))
    )
    (net (code "40") (name "Net-(P3-Pad1)") (class "Default")
      (node (ref "P3") (pin "1") (pintype "passive"))
      (node (ref "R13") (pin "2") (pinfunction "2_2") (pintype "passive"))
    )
    (net (code "41") (name "Net-(R11-Pad1)") (class "Default")
      (node (ref "R11") (pin "1") (pinfunction "1_1") (pintype "passive"))
      (node (ref "U6") (pin "3") (pintype "passive"))
    )
    (net (code "42") (name "Net-(R11-Pad2)") (class "Default")
      (node (ref "R11") (pin "2") (pinfunction "2_2") (pintype "passive"))
      (node (ref "RP2") (pin "1") (pinfunction "1_1") (pintype "passive"))
    )
    (net (code "43") (name "Net-(R13-Pad1)") (class "Default")
      (node (ref "R13") (pin "1") (pinfunction "1_1") (pintype "passive"))
      (node (ref "U6") (pin "6") (pintype "passive"))
      (node (ref "U6") (pin "7") (pintype "passive"))
    )
    (net (code "44") (name "Net-(R14-Pad2)") (class "Default")
      (node (ref "R14") (pin "2") (pinfunction "2_2") (pintype "passive"))
      (node (ref "R15") (pin "2") (pinfunction "2_2") (pintype "passive"))
      (node (ref "U6") (pin "2") (pintype "passive"))
    )
    (net (code "45") (name "Net-(R15-Pad1)") (class "Default")
      (node (ref "R15") (pin "1") (pinfunction "1_1") (pintype "passive"))
      (node (ref "RP3") (pin "3") (pinfunction "3_3") (pintype "passive"))
    )
    (net (code "46") (name "Net-(RP2-Pad2)") (class "Default")
      (node (ref "RP2") (pin "2") (pinfunction "2_2") (pintype "passive"))
      (node (ref "RP2") (pin "3") (pinfunction "3_3") (pintype "passive"))
      (node (ref "U6") (pin "1") (pintype "passive"))
      (node (ref "U6") (pin "5") (pintype "passive"))
    )
    (net (code "47") (name "Net-(U2-LEDK)") (class "Default")
      (node (ref "R2") (pin "1") (pinfunction "1_1") (pintype "passive"))
      (node (ref "U2") (pin "2") (pinfunction "LEDK_2") (pintype "passive"))
    )
    (net (code "48") (name "Net-(U3-CAP+)") (class "Default")
      (node (ref "C6") (pin "2") (pinfunction "2_2") (pintype "passive"))
      (node (ref "U3") (pin "2") (pinfunction "CAP+_2") (pintype "passive"))
    )
    (net (code "49") (name "Net-(U3-CAP-)") (class "Default")
      (node (ref "C6") (pin "1") (pinfunction "1_1") (pintype "passive"))
      (node (ref "U3") (pin "4") (pinfunction "CAP-_4") (pintype "passive"))
    )
    (net (code "50") (name "Net-(U4-BOOT0)") (class "Default")
      (node (ref "R10") (pin "1") (pinfunction "1_1") (pintype "passive"))
      (node (ref "U4") (pin "44") (pinfunction "BOOT0_44") (pintype "input"))
    )
    (net (code "51") (name "Net-(U4-PB2{slash}BOOT1)") (class "Default")
      (node (ref "R3") (pin "2") (pinfunction "2_2") (pintype "passive"))
      (node (ref "U4") (pin "20") (pinfunction "PB2/BOOT1_20") (pintype "bidirectional"))
    )
    (net (code "52") (name "Net-(U5-QOUTA)") (class "Default")
      (node (ref "P1") (pin "1") (pintype "passive"))
      (node (ref "U5") (pin "14") (pinfunction "QOUTA_14") (pintype "passive"))
    )
    (net (code "53") (name "Net-(U5-Rset)") (class "Default")
      (node (ref "R6") (pin "2") (pinfunction "2_2") (pintype "passive"))
      (node (ref "U5") (pin "12") (pinfunction "Rset_12") (pintype "passive"))
    )
    (net (code "54") (name "Net-(U5-VINN)") (class "Default")
      (node (ref "RP1") (pin "3") (pinfunction "3_3") (pintype "passive"))
      (node (ref "U5") (pin "15") (pinfunction "VINN_15") (pintype "passive"))
    )
    (net (code "55") (name "VCC") (class "Default")
      (node (ref "C12") (pin "2") (pinfunction "2_2") (pintype "passive"))
      (node (ref "C13") (pin "2") (pinfunction "2_2") (pintype "passive"))
      (node (ref "C2") (pin "1") (pinfunction "1_1") (pintype "passive"))
      (node (ref "C4") (pin "2") (pinfunction "2_2") (pintype "passive"))
      (node (ref "R1") (pin "2") (pinfunction "2_2") (pintype "passive"))
      (node (ref "R12") (pin "2") (pinfunction "2_2") (pintype "passive"))
      (node (ref "R3") (pin "1") (pinfunction "1_1") (pintype "passive"))
      (node (ref "U1") (pin "5") (pinfunction "Vout_5") (pintype "passive"))
      (node (ref "U2") (pin "3") (pinfunction "LEDA_3") (pintype "passive"))
      (node (ref "U2") (pin "4") (pinfunction "VDD_4") (pintype "passive"))
      (node (ref "U4") (pin "24") (pinfunction "VDD_1_24") (pintype "power_in"))
      (node (ref "U4") (pin "36") (pinfunction "VDD_2_36") (pintype "power_in"))
      (node (ref "U4") (pin "48") (pinfunction "VDD_3_48") (pintype "power_in"))
      (node (ref "U4") (pin "9") (pinfunction "VDDA_9") (pintype "power_in"))
    )
    (net (code "56") (name "unconnected-(CR1-NC-Pad1)") (class "Default")
      (node (ref "CR1") (pin "1") (pinfunction "NC_1") (pintype "passive"))
    )
    (net (code "57") (name "unconnected-(S1-NO-Pad3)") (class "Default")
      (node (ref "S1") (pin "3") (pinfunction "NO_3") (pintype "passive"))
    )
    (net (code "58") (name "unconnected-(U1-NC-Pad4)") (class "Default")
      (node (ref "U1") (pin "4") (pinfunction "NC_4") (pintype "passive"))
    )
    (net (code "59") (name "unconnected-(U3-0SC-Pad7)") (class "Default")
      (node (ref "U3") (pin "7") (pinfunction "0SC_7") (pintype "passive"))
    )
    (net (code "60") (name "unconnected-(U3-NC-Pad1)") (class "Default")
      (node (ref "U3") (pin "1") (pinfunction "NC_1") (pintype "passive"))
    )
    (net (code "61") (name "unconnected-(U4-PA8-Pad29)") (class "Default")
      (node (ref "U4") (pin "29") (pinfunction "PA8_29") (pintype "bidirectional"))
    )
    (net (code "62") (name "unconnected-(U4-PA9-Pad30)") (class "Default")
      (node (ref "U4") (pin "30") (pinfunction "PA9_30") (pintype "bidirectional"))
    )
    (net (code "63") (name "unconnected-(U4-PA10-Pad31)") (class "Default")
      (node (ref "U4") (pin "31") (pinfunction "PA10_31") (pintype "bidirectional"))
    )
    (net (code "64") (name "unconnected-(U4-PA15{slash}JTDI-Pad38)") (class "Default")
      (node (ref "U4") (pin "38") (pinfunction "PA15/JTDI_38") (pintype "bidirectional"))
    )
    (net (code "65") (name "unconnected-(U4-PB3{slash}JTDO-Pad39)") (class "Default")
      (node (ref "U4") (pin "39") (pinfunction "PB3/JTDO_39") (pintype "bidirectional"))
    )
    (net (code "66") (name "unconnected-(U4-PB4{slash}JNTRST-Pad40)") (class "Default")
      (node (ref "U4") (pin "40") (pinfunction "PB4/JNTRST_40") (pintype "bidirectional"))
    )
    (net (code "67") (name "unconnected-(U4-PB11-Pad22)") (class "Default")
      (node (ref "U4") (pin "22") (pinfunction "PB11_22") (pintype "bidirectional"))
    )
    (net (code "68") (name "unconnected-(U4-PC13-TAMPER-RTC-Pad2)") (class "Default")
      (node (ref "U4") (pin "2") (pinfunction "PC13-TAMPER-RTC_2") (pintype "bidirectional"))
    )
    (net (code "69") (name "unconnected-(U4-PC14-OSC32_IN-Pad3)") (class "Default")
      (node (ref "U4") (pin "3") (pinfunction "PC14-OSC32_IN_3") (pintype "bidirectional"))
    )
    (net (code "70") (name "unconnected-(U4-PC15-OSC32_OUT-Pad4)") (class "Default")
      (node (ref "U4") (pin "4") (pinfunction "PC15-OSC32_OUT_4") (pintype "bidirectional"))
    )
    (net (code "71") (name "unconnected-(U4-VBAT-Pad1)") (class "Default")
      (node (ref "U4") (pin "1") (pinfunction "VBAT_1") (pintype "power_in"))
    )
    (net (code "72") (name "unconnected-(U5-DACBL-Pad17)") (class "Default")
      (node (ref "U5") (pin "17") (pinfunction "DACBL_17") (pintype "passive"))
    )
    (net (code "73") (name "unconnected-(U5-QOUTB-Pad13)") (class "Default")
      (node (ref "U5") (pin "13") (pinfunction "QOUTB_13") (pintype "passive"))
    )
    (net (code "74") (name "unconnected-(USB1-CC1-PadA5)") (class "Default")
      (node (ref "USB1") (pin "A5") (pinfunction "CC1_A5") (pintype "passive"))
    )
    (net (code "75") (name "unconnected-(USB1-CC2-PadB5)") (class "Default")
      (node (ref "USB1") (pin "B5") (pinfunction "CC2_B5") (pintype "passive"))
    )
    (net (code "76") (name "unconnected-(USB1-RX1+-PadB11)") (class "Default")
      (node (ref "USB1") (pin "B11") (pinfunction "RX1+_B11") (pintype "passive"))
    )
    (net (code "77") (name "unconnected-(USB1-RX1--PadB10)") (class "Default")
      (node (ref "USB1") (pin "B10") (pinfunction "RX1-_B10") (pintype "passive"))
    )
    (net (code "78") (name "unconnected-(USB1-RX2+-PadA11)") (class "Default")
      (node (ref "USB1") (pin "A11") (pinfunction "RX2+_A11") (pintype "passive"))
    )
    (net (code "79") (name "unconnected-(USB1-RX2--PadA10)") (class "Default")
      (node (ref "USB1") (pin "A10") (pinfunction "RX2-_A10") (pintype "passive"))
    )
    (net (code "80") (name "unconnected-(USB1-SBU1-PadA8)") (class "Default")
      (node (ref "USB1") (pin "A8") (pinfunction "SBU1_A8") (pintype "passive"))
    )
    (net (code "81") (name "unconnected-(USB1-SBU2-PadB8)") (class "Default")
      (node (ref "USB1") (pin "B8") (pinfunction "SBU2_B8") (pintype "passive"))
    )
    (net (code "82") (name "unconnected-(USB1-SH1-Pad1)") (class "Default")
      (node (ref "USB1") (pin "1") (pinfunction "SH1_1") (pintype "passive"))
    )
    (net (code "83") (name "unconnected-(USB1-SH2-Pad2)") (class "Default")
      (node (ref "USB1") (pin "2") (pinfunction "SH2_2") (pintype "passive"))
    )
    (net (code "84") (name "unconnected-(USB1-SH3-Pad3)") (class "Default")
      (node (ref "USB1") (pin "3") (pinfunction "SH3_3") (pintype "passive"))
    )
    (net (code "85") (name "unconnected-(USB1-SH4-Pad4)") (class "Default")
      (node (ref "USB1") (pin "4") (pinfunction "SH4_4") (pintype "passive"))
    )
    (net (code "86") (name "unconnected-(USB1-TX1+-PadA2)") (class "Default")
      (node (ref "USB1") (pin "A2") (pinfunction "TX1+_A2") (pintype "passive"))
    )
    (net (code "87") (name "unconnected-(USB1-TX1--PadA3)") (class "Default")
      (node (ref "USB1") (pin "A3") (pinfunction "TX1-_A3") (pintype "passive"))
    )
    (net (code "88") (name "unconnected-(USB1-TX2+-PadB2)") (class "Default")
      (node (ref "USB1") (pin "B2") (pinfunction "TX2+_B2") (pintype "passive"))
    )
    (net (code "89") (name "unconnected-(USB1-TX2--PadB3)") (class "Default")
      (node (ref "USB1") (pin "B3") (pinfunction "TX2-_B3") (pintype "passive"))
    )
  )
)
